# ProPrj_PGEKI_MAIN_2025-10-30.net
KiCad netlist of a schematic drawn in EasyEDA Pro
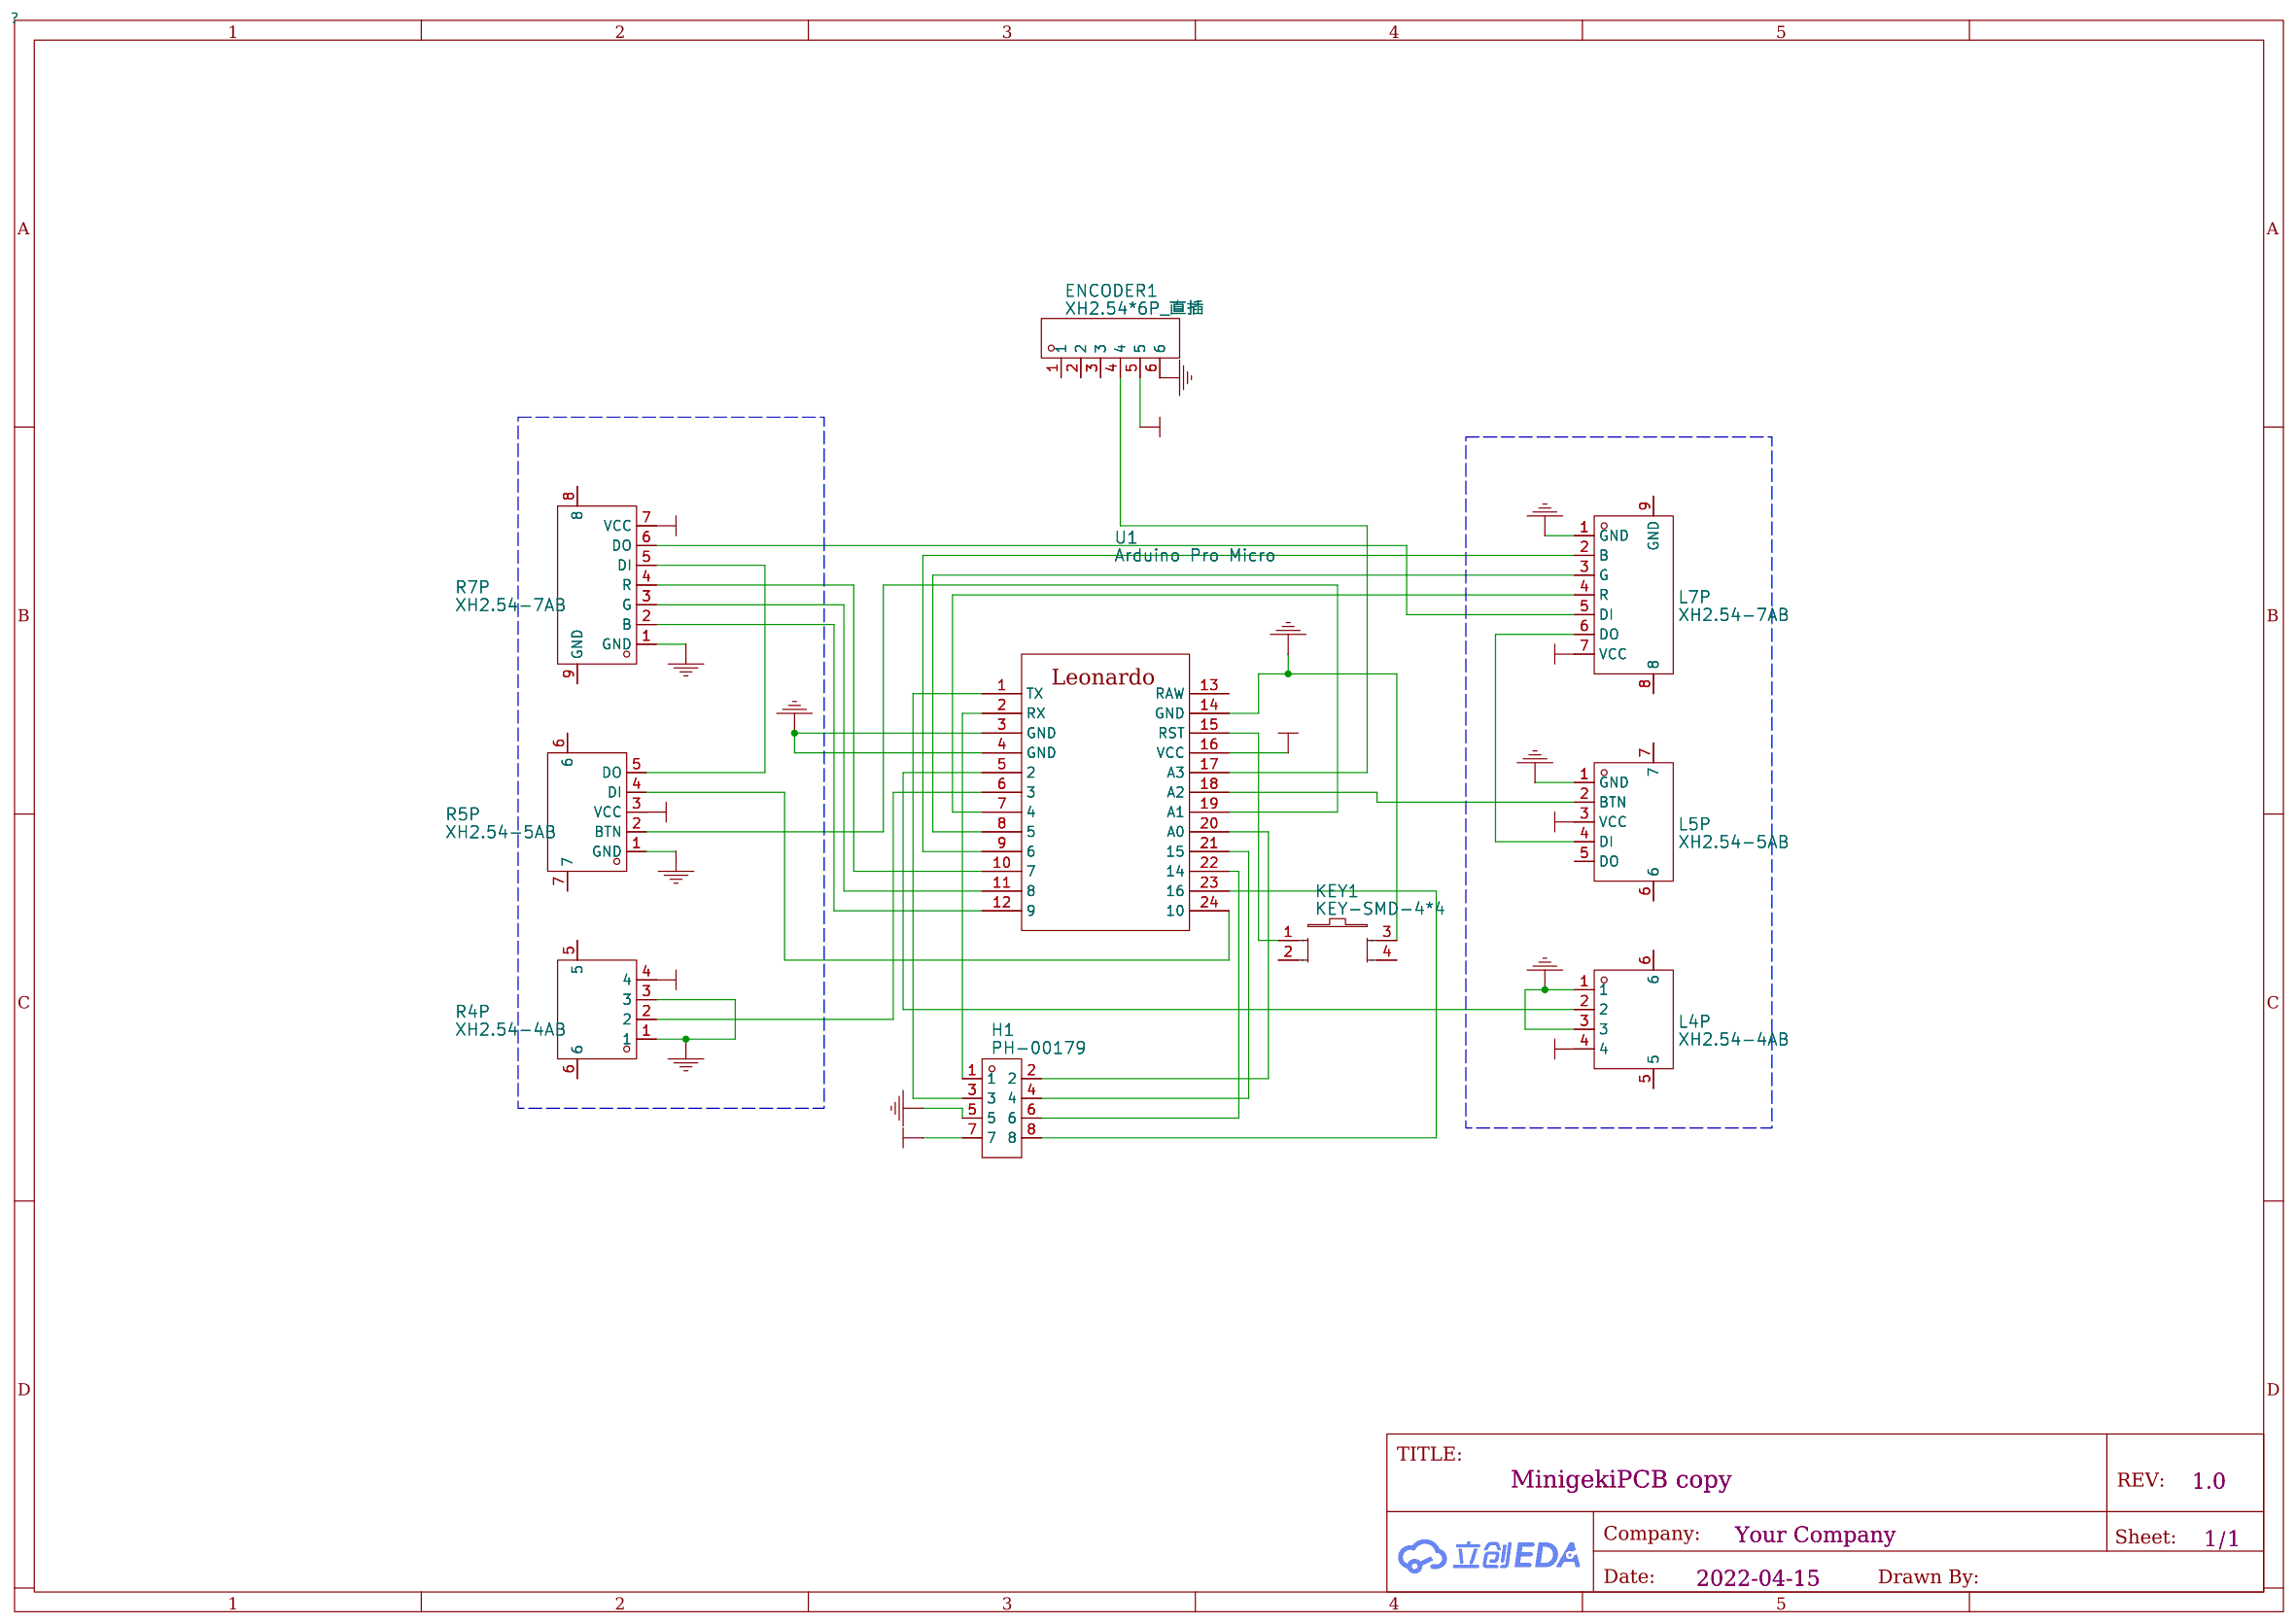
[diagram p0: main]
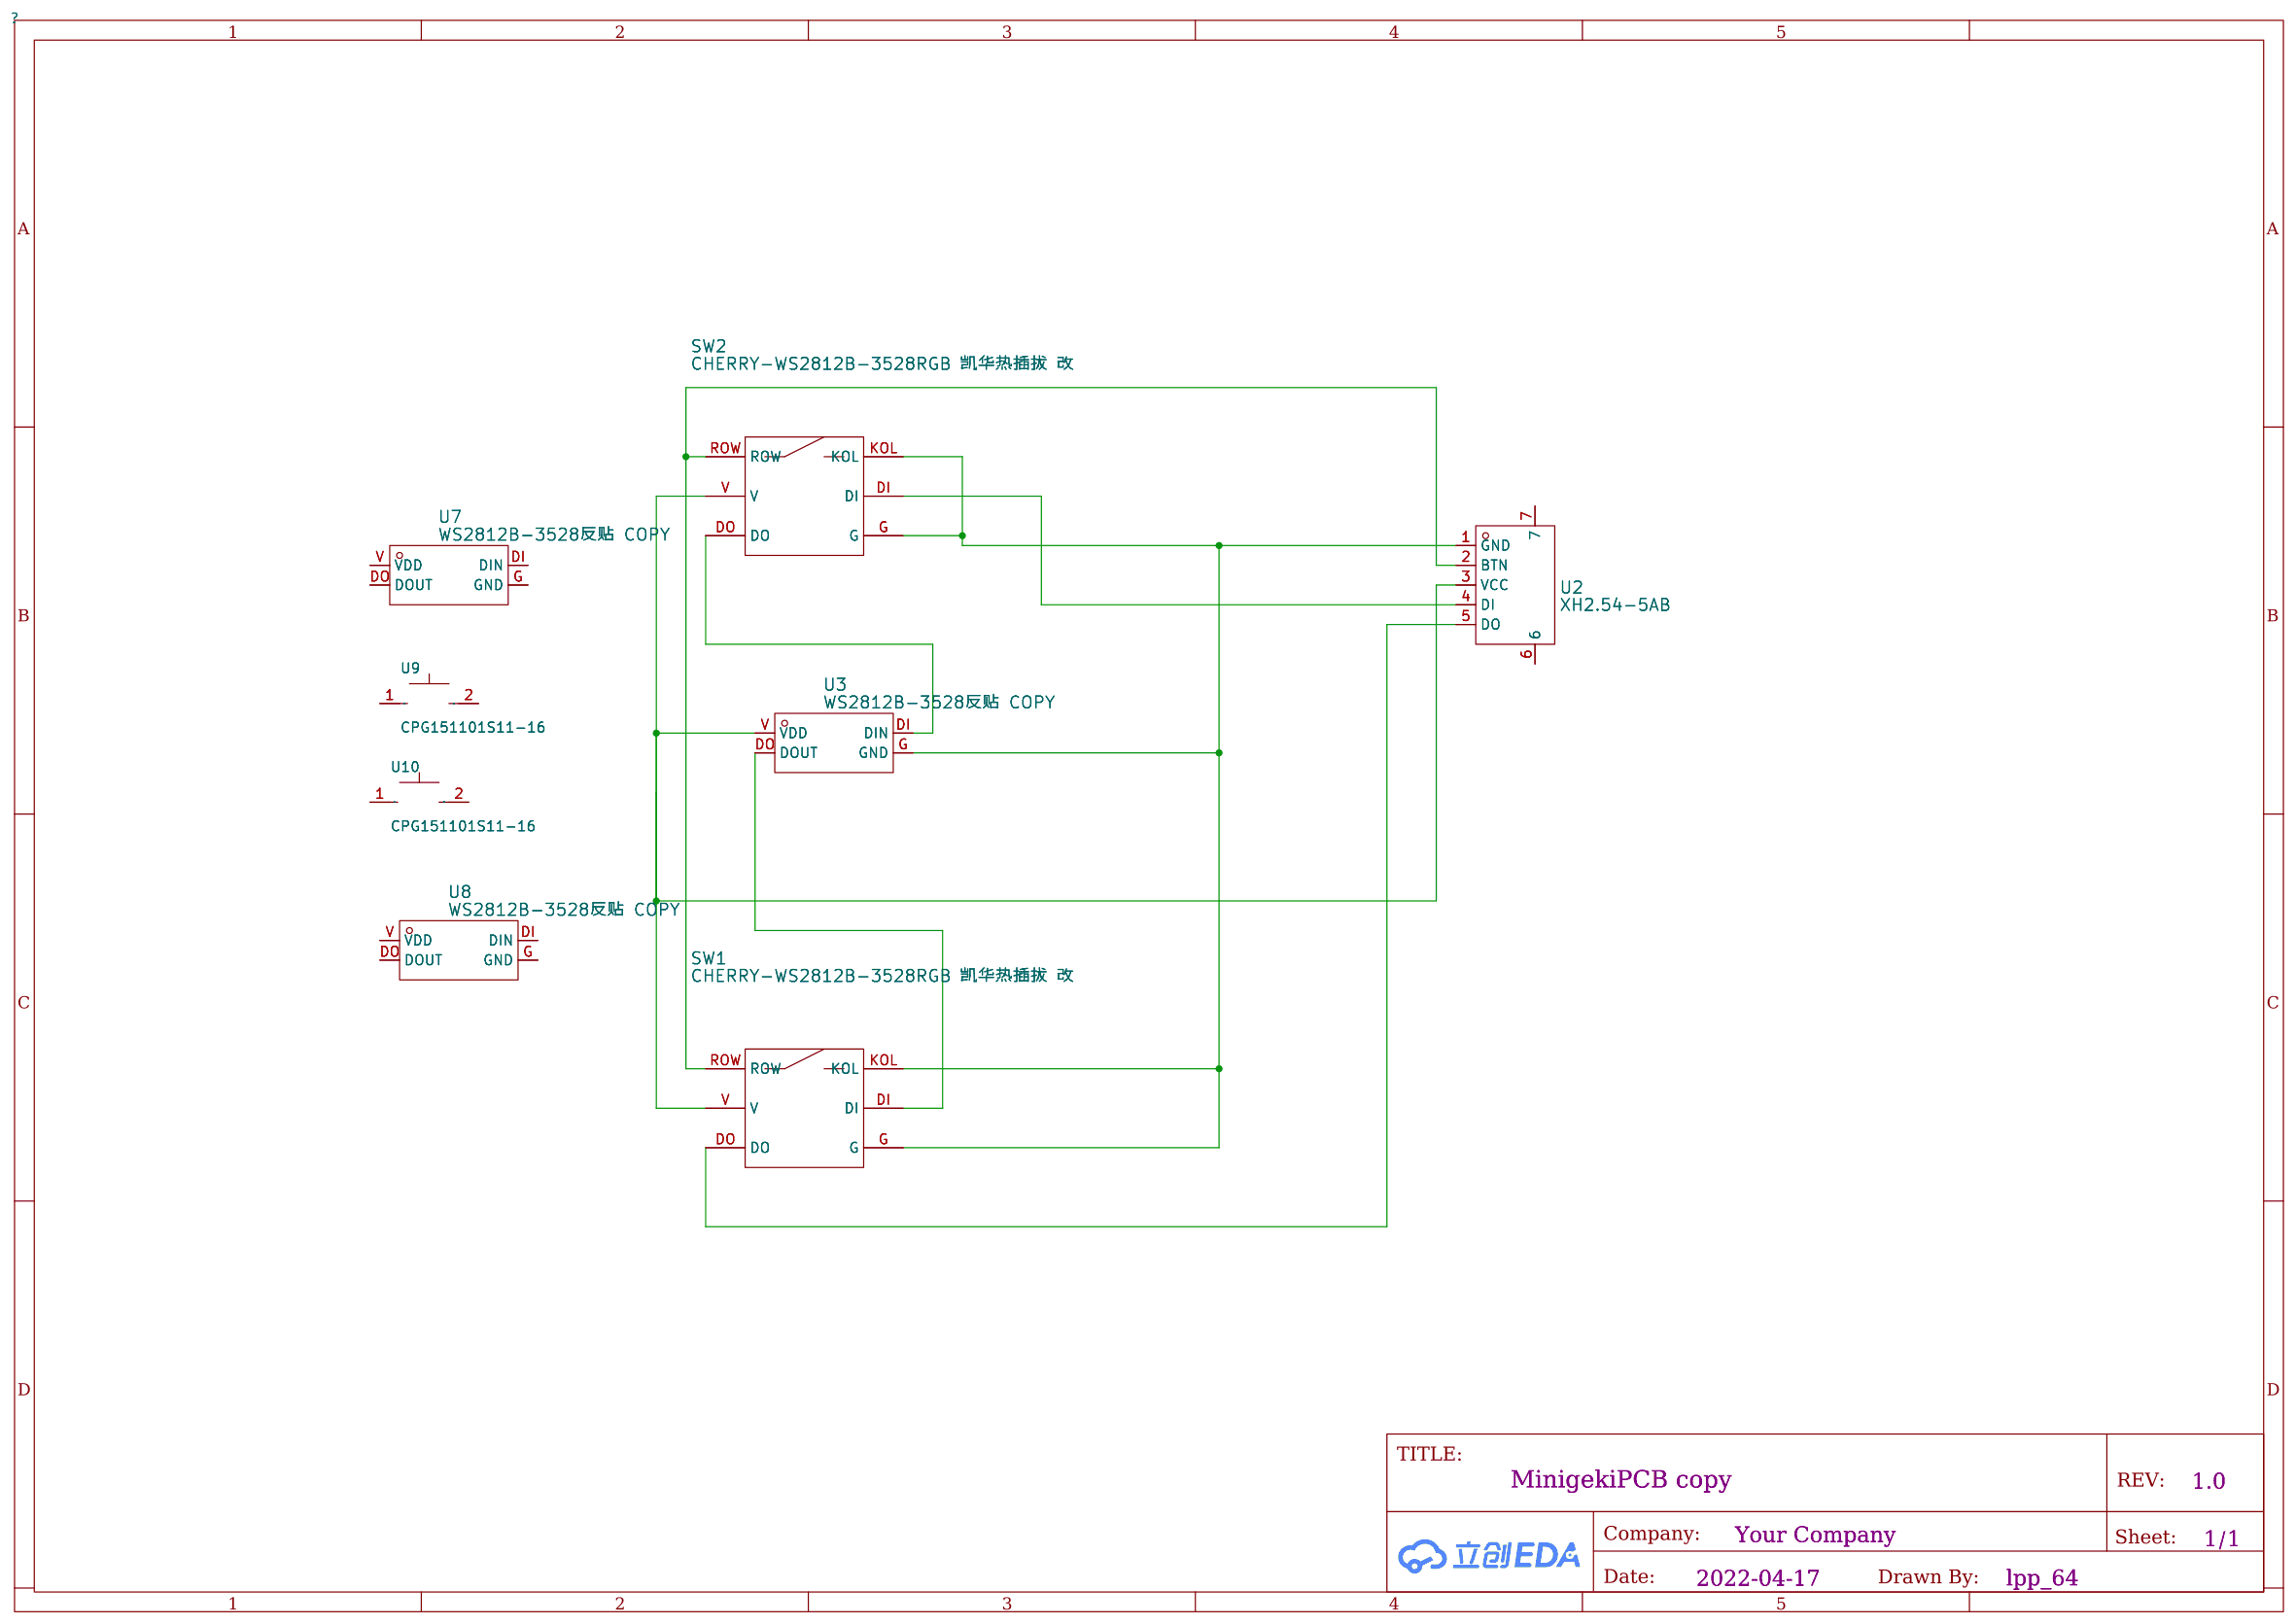
[diagram p1: Sheet_2]
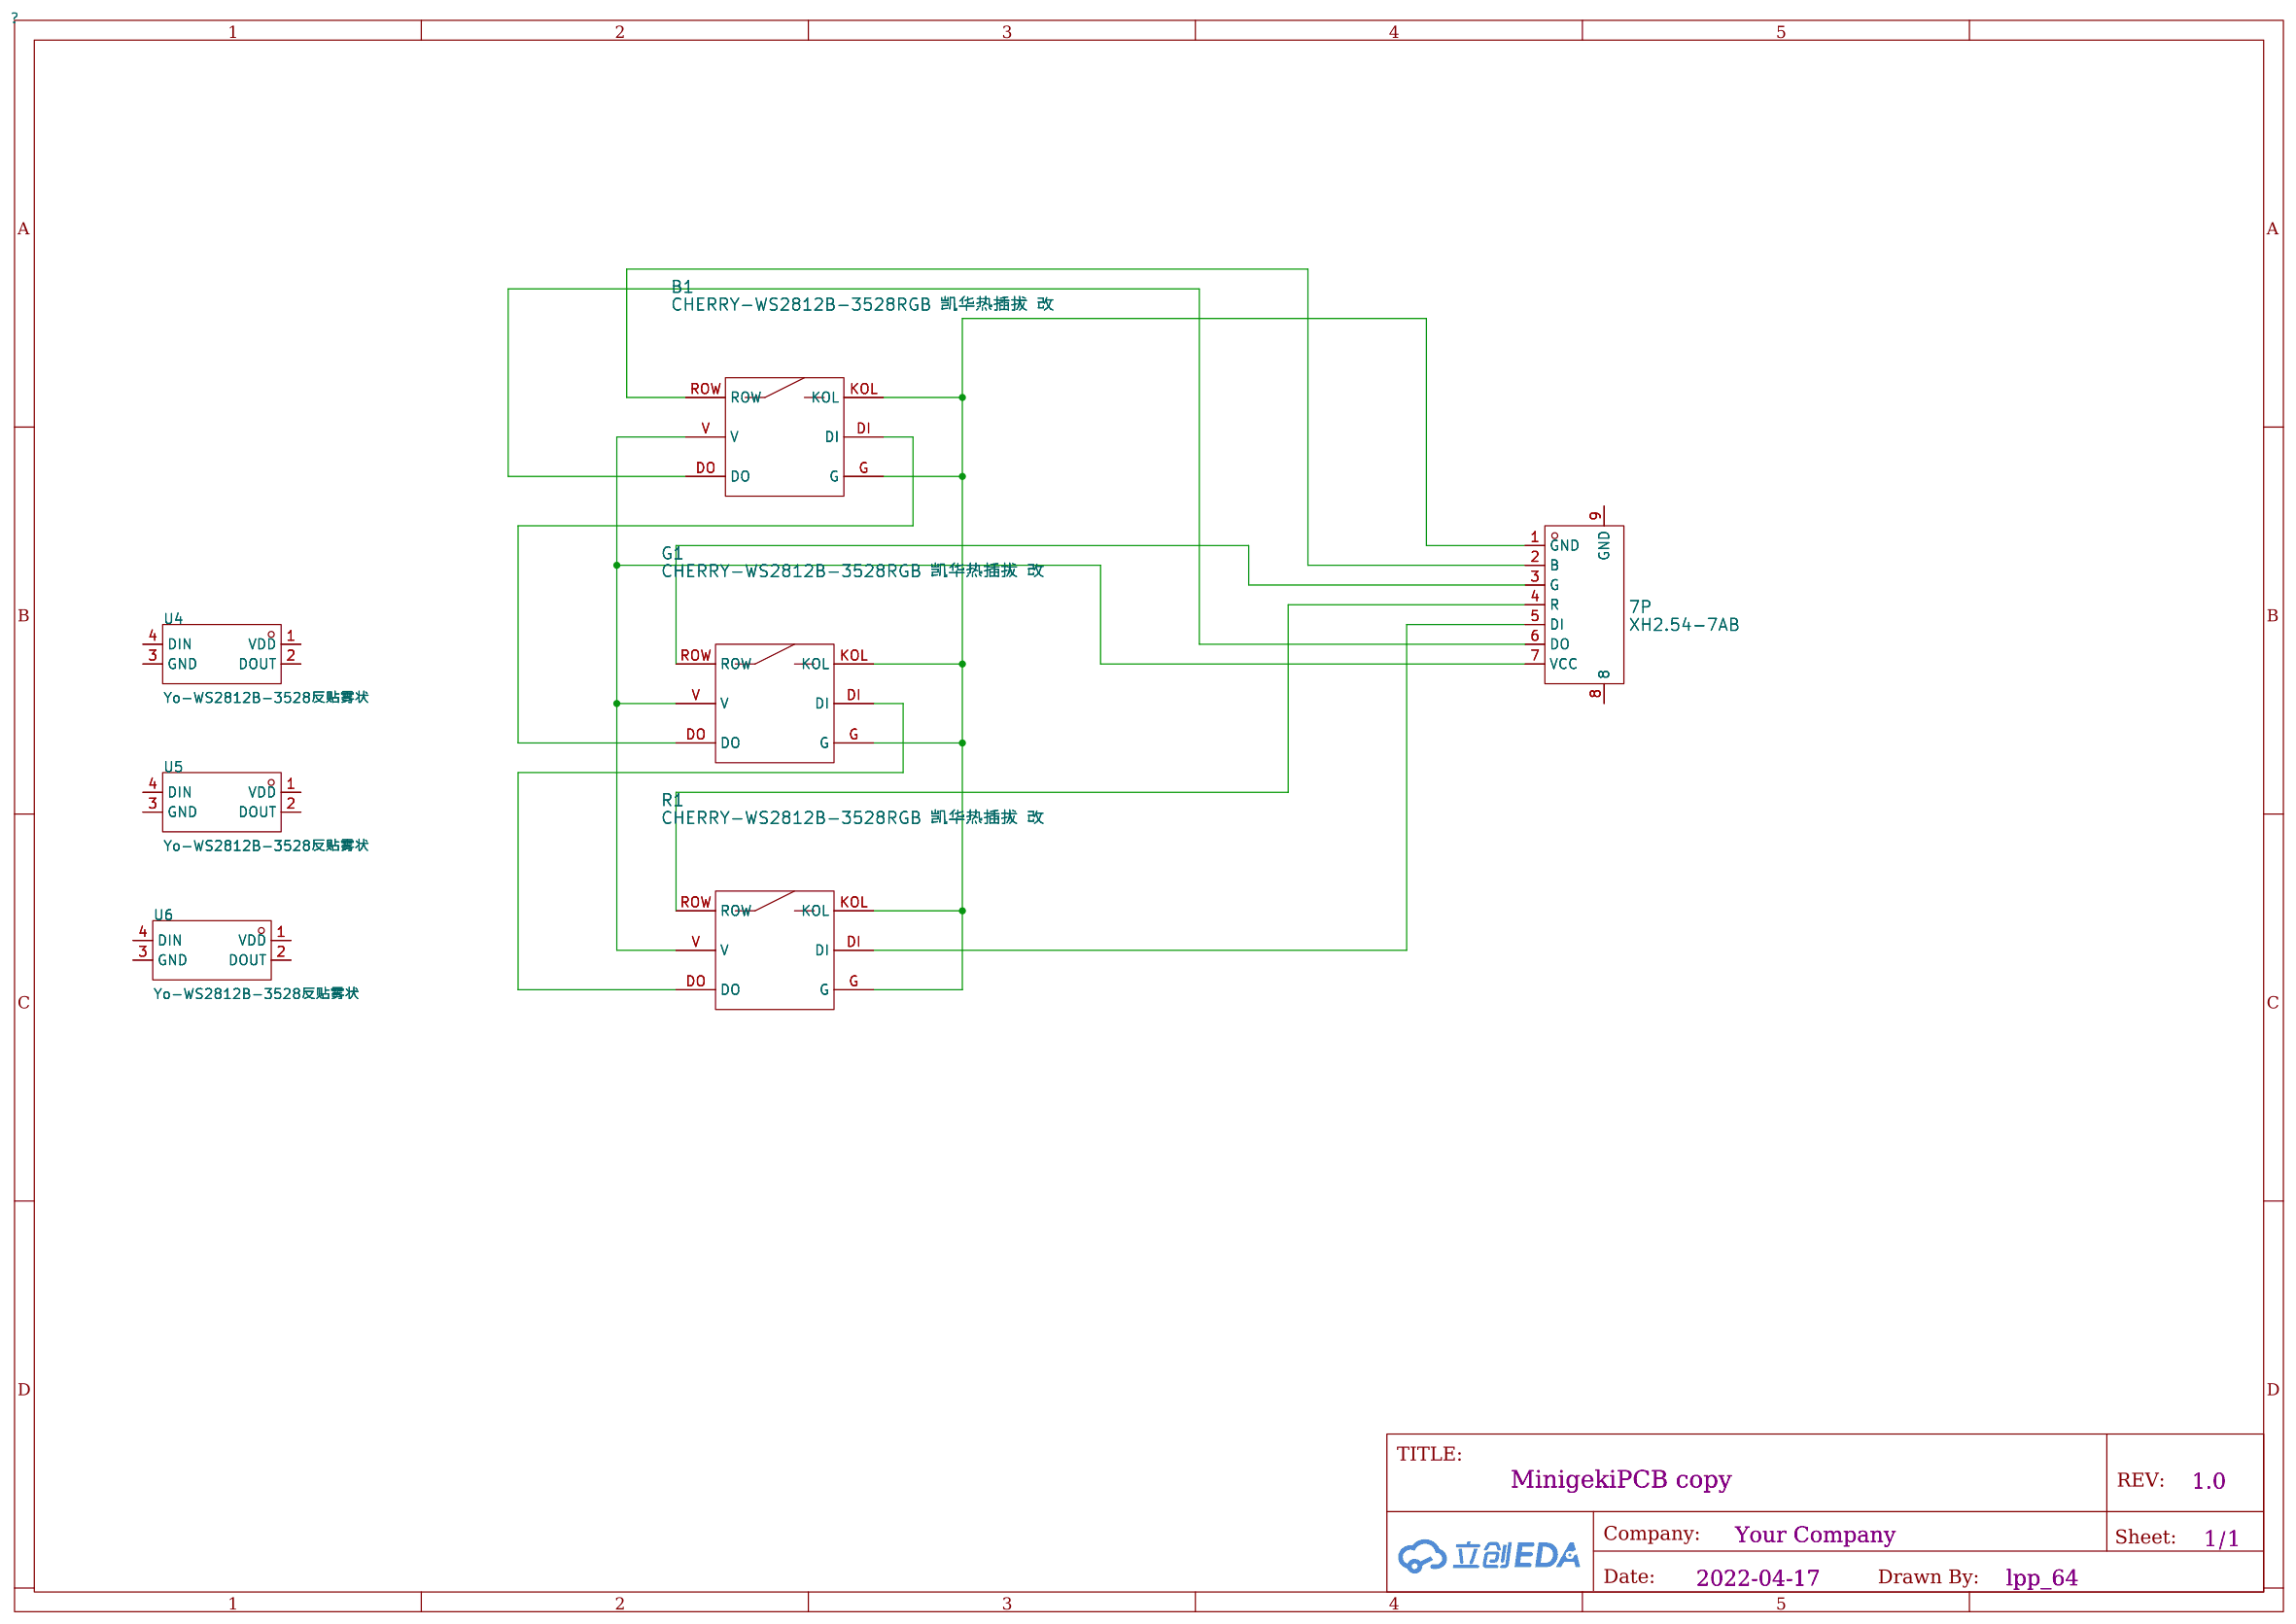
[diagram p2: Sheet_3]

(export (version "E")
  (design (tool "Eeschema 10.0.6"))
  (components
    (comp (ref "ENCODER1")
      (value "XH2.54*6P_直插")
      (footprint "easyedapro:CONN-TH_XH2.54-6P")
      (libsource (lib "easyedapro") (part "XH2.54*6P_直插"))
    )
    (comp (ref "H1")
      (value "PH-00179")
      (footprint "easyedapro:HDR-TH_8P-P2.54-V-M-R2-C4-S2.54")
      (fields (field (name "Manufacturer") "Liansheng(连盛)"))
      (libsource (lib "easyedapro") (part "PH-00179"))
    )
    (comp (ref "KEY1")
      (value "KEY-SMD-4*4")
      (footprint "easyedapro:SW-SMD_4P-L5.2-W5.2-P3.70-LS6.5")
      (libsource (lib "easyedapro") (part "KEY-SMD-4*4"))
    )
    (comp (ref "L4P")
      (value "XH2.54-4AB")
      (footprint "easyedapro:CONN-SMD_4P-P2.54_XH2.54-4AB")
      (fields (field (name "Manufacturer") "Boom Precision Elec"))
      (libsource (lib "easyedapro") (part "XH2.54-4AB"))
    )
    (comp (ref "L5P")
      (value "XH2.54-5AB")
      (footprint "easyedapro:CONN-SMD_5P-P2.54_XH2.54-5AB")
      (fields (field (name "Manufacturer") "Boom Precision Elec"))
      (libsource (lib "easyedapro") (part "XH2.54-5AB"))
    )
    (comp (ref "L7P")
      (value "XH2.54-7AB")
      (footprint "easyedapro:CONN-SMD_7P-P2.54_XH2.54-7AB")
      (fields (field (name "Manufacturer") "Boom Precision Elec"))
      (libsource (lib "easyedapro") (part "XH2.54-7AB"))
    )
    (comp (ref "R4P")
      (value "XH2.54-4AB")
      (footprint "easyedapro:CONN-SMD_4P-P2.54_XH2.54-4AB")
      (fields (field (name "Manufacturer") "Boom Precision Elec"))
      (libsource (lib "easyedapro") (part "XH2.54-4AB"))
    )
    (comp (ref "R5P")
      (value "XH2.54-5AB")
      (footprint "easyedapro:CONN-SMD_5P-P2.54_XH2.54-5AB")
      (fields (field (name "Manufacturer") "Boom Precision Elec"))
      (libsource (lib "easyedapro") (part "XH2.54-5AB"))
    )
    (comp (ref "R7P")
      (value "XH2.54-7AB")
      (footprint "easyedapro:CONN-SMD_7P-P2.54_XH2.54-7AB")
      (fields (field (name "Manufacturer") "Boom Precision Elec"))
      (libsource (lib "easyedapro") (part "XH2.54-7AB"))
    )
    (comp (ref "U1")
      (value "Arduino Pro Micro")
      (footprint "easyedapro:PROMICRO")
      (libsource (lib "easyedapro") (part "Arduino Pro Micro"))
    )
    (comp (ref "SW1")
      (value "CHERRY-WS2812B-3528RGB 凯华热插拔 改")
      (footprint "easyedapro:凯华热插拔-WS2812-3528灯反贴-带二极管-KAILH-IN4148-3528")
      (fields (field (name "Manufacturer Part") "CherryMX"))
      (libsource (lib "easyedapro") (part "CHERRY-WS2812B-3528RGB 凯华热插拔 改 无二极管"))
    )
    (comp (ref "SW2")
      (value "CHERRY-WS2812B-3528RGB 凯华热插拔 改")
      (footprint "easyedapro:凯华热插拔-WS2812-3528灯反贴-带二极管-KAILH-IN4148-3528")
      (fields (field (name "Manufacturer Part") "CherryMX"))
      (libsource (lib "easyedapro") (part "CHERRY-WS2812B-3528RGB 凯华热插拔 改 无二极管"))
    )
    (comp (ref "U2")
      (value "XH2.54-5AB")
      (footprint "easyedapro:CONN-SMD_5P-P2.54_XH2.54-5AB")
      (fields (field (name "Manufacturer") "Boom Precision Elec"))
      (libsource (lib "easyedapro") (part "XH2.54-5AB"))
    )
    (comp (ref "U3")
      (value "WS2812B-3528反贴 COPY")
      (footprint "easyedapro:WS2812-3528-反贴")
      (fields (field (name "Manufacturer Part") "Yo-WS2812B-3528反贴雾状"))
      (libsource (lib "easyedapro") (part "WS2812B-3528反贴 COPY"))
    )
    (comp (ref "U7")
      (value "WS2812B-3528反贴 COPY")
      (footprint "easyedapro:WS2812-3528-反贴")
      (fields (field (name "Manufacturer Part") "Yo-WS2812B-3528反贴雾状"))
      (libsource (lib "easyedapro") (part "WS2812B-3528反贴 COPY"))
    )
    (comp (ref "U8")
      (value "WS2812B-3528反贴 COPY")
      (footprint "easyedapro:WS2812-3528-反贴")
      (fields (field (name "Manufacturer Part") "Yo-WS2812B-3528反贴雾状"))
      (libsource (lib "easyedapro") (part "WS2812B-3528反贴 COPY"))
    )
    (comp (ref "U9")
      (value "CPG151101S11-16")
      (footprint "easyedapro:SMD_KEYBOARD-SW")
      (description "轴类型:-;工作电压:2V~12V;操作力:-;触底力:-;触发行程:-;总行程:-;针脚数:-;机械寿命:-;工作温度:-;")
      (fields (field (name "Manufacturer") "Kailh(凯华)"))
      (libsource (lib "easyedapro") (part "CPG151101S11-16"))
    )
    (comp (ref "U10")
      (value "CPG151101S11-16")
      (footprint "easyedapro:SMD_KEYBOARD-SW")
      (description "轴类型:-;工作电压:2V~12V;操作力:-;触底力:-;触发行程:-;总行程:-;针脚数:-;机械寿命:-;工作温度:-;")
      (fields (field (name "Manufacturer") "Kailh(凯华)"))
      (libsource (lib "easyedapro") (part "CPG151101S11-16"))
    )
    (comp (ref "7P")
      (value "XH2.54-7AB")
      (footprint "easyedapro:CONN-SMD_7P-P2.54_XH2.54-7AB")
      (fields (field (name "Manufacturer") "Boom Precision Elec"))
      (libsource (lib "easyedapro") (part "XH2.54-7AB"))
    )
    (comp (ref "B1")
      (value "CHERRY-WS2812B-3528RGB 凯华热插拔 改")
      (footprint "easyedapro:凯华热插拔-WS2812-3528灯反贴-带二极管-KAILH-IN4148-3528")
      (fields (field (name "Manufacturer Part") "CherryMX"))
      (libsource (lib "easyedapro") (part "CHERRY-WS2812B-3528RGB 凯华热插拔 改 无二极管"))
    )
    (comp (ref "G1")
      (value "CHERRY-WS2812B-3528RGB 凯华热插拔 改")
      (footprint "easyedapro:凯华热插拔-WS2812-3528灯反贴-带二极管-KAILH-IN4148-3528")
      (fields (field (name "Manufacturer Part") "CherryMX"))
      (libsource (lib "easyedapro") (part "CHERRY-WS2812B-3528RGB 凯华热插拔 改 无二极管"))
    )
    (comp (ref "R1")
      (value "CHERRY-WS2812B-3528RGB 凯华热插拔 改")
      (footprint "easyedapro:凯华热插拔-WS2812-3528灯反贴-带二极管-KAILH-IN4148-3528")
      (fields (field (name "Manufacturer Part") "CherryMX"))
      (libsource (lib "easyedapro") (part "CHERRY-WS2812B-3528RGB 凯华热插拔 改 无二极管"))
    )
    (comp (ref "U4")
      (value "Yo-WS2812B-3528反贴雾状")
      (footprint "easyedapro:LED-SMD_L3.2-W2.8-BR_DY-S352818")
      (libsource (lib "easyedapro") (part "YO-WS2812B-3528_C9900003682"))
    )
    (comp (ref "U5")
      (value "Yo-WS2812B-3528反贴雾状")
      (footprint "easyedapro:LED-SMD_L3.2-W2.8-BR_DY-S352818")
      (libsource (lib "easyedapro") (part "YO-WS2812B-3528_C9900003682"))
    )
    (comp (ref "U6")
      (value "Yo-WS2812B-3528反贴雾状")
      (footprint "easyedapro:LED-SMD_L3.2-W2.8-BR_DY-S352818")
      (libsource (lib "easyedapro") (part "YO-WS2812B-3528_C9900003682"))
    )
  )
  (nets
    (net (code "1") (name "GND") (class "Default")
      (node (ref "ENCODER1") (pin "6") (pinfunction "6_6") (pintype "input"))
      (node (ref "H1") (pin "5") (pinfunction "5_5") (pintype "input"))
      (node (ref "KEY1") (pin "3") (pinfunction "3_3") (pintype "input"))
      (node (ref "L4P") (pin "1") (pinfunction "1_1") (pintype "input"))
      (node (ref "L4P") (pin "3") (pinfunction "3_3") (pintype "input"))
      (node (ref "L5P") (pin "1") (pinfunction "GND_1") (pintype "input"))
      (node (ref "L7P") (pin "1") (pinfunction "GND_1") (pintype "input"))
      (node (ref "R4P") (pin "1") (pinfunction "1_1") (pintype "input"))
      (node (ref "R4P") (pin "3") (pinfunction "3_3") (pintype "input"))
      (node (ref "R5P") (pin "1") (pinfunction "GND_1") (pintype "input"))
      (node (ref "R7P") (pin "1") (pinfunction "GND_1") (pintype "input"))
      (node (ref "U1") (pin "14") (pinfunction "GND_14") (pintype "input"))
      (node (ref "U1") (pin "3") (pinfunction "GND_3") (pintype "input"))
      (node (ref "U1") (pin "4") (pinfunction "GND_4") (pintype "input"))
    )
    (net (code "2") (name "Net-(7P-B)") (class "Default")
      (node (ref "7P") (pin "2") (pinfunction "B_2") (pintype "input"))
      (node (ref "B1") (pin "ROW") (pinfunction "ROW_ROW") (pintype "input"))
    )
    (net (code "3") (name "Net-(7P-DI)") (class "Default")
      (node (ref "7P") (pin "5") (pinfunction "DI_5") (pintype "input"))
      (node (ref "R1") (pin "DI") (pinfunction "DI_DI") (pintype "input"))
    )
    (net (code "4") (name "Net-(7P-DO)") (class "Default")
      (node (ref "7P") (pin "6") (pinfunction "DO_6") (pintype "input"))
      (node (ref "B1") (pin "DO") (pinfunction "DO_DO") (pintype "input"))
    )
    (net (code "5") (name "Net-(7P-G)") (class "Default")
      (node (ref "7P") (pin "3") (pinfunction "G_3") (pintype "input"))
      (node (ref "G1") (pin "ROW") (pinfunction "ROW_ROW") (pintype "input"))
    )
    (net (code "6") (name "Net-(7P-GND-Pad1)") (class "Default")
      (node (ref "7P") (pin "1") (pinfunction "GND_1") (pintype "input"))
      (node (ref "B1") (pin "G") (pinfunction "G_G") (pintype "input"))
      (node (ref "B1") (pin "KOL") (pinfunction "KOL_KOL") (pintype "input"))
      (node (ref "G1") (pin "G") (pinfunction "G_G") (pintype "input"))
      (node (ref "G1") (pin "KOL") (pinfunction "KOL_KOL") (pintype "input"))
      (node (ref "R1") (pin "G") (pinfunction "G_G") (pintype "input"))
      (node (ref "R1") (pin "KOL") (pinfunction "KOL_KOL") (pintype "input"))
    )
    (net (code "7") (name "Net-(7P-R)") (class "Default")
      (node (ref "7P") (pin "4") (pinfunction "R_4") (pintype "input"))
      (node (ref "R1") (pin "ROW") (pinfunction "ROW_ROW") (pintype "input"))
    )
    (net (code "8") (name "Net-(7P-VCC)") (class "Default")
      (node (ref "7P") (pin "7") (pinfunction "VCC_7") (pintype "input"))
      (node (ref "B1") (pin "V") (pinfunction "V_V") (pintype "input"))
      (node (ref "G1") (pin "V") (pinfunction "V_V") (pintype "input"))
      (node (ref "R1") (pin "V") (pinfunction "V_V") (pintype "input"))
    )
    (net (code "9") (name "Net-(B1-PadDI)") (class "Default")
      (node (ref "B1") (pin "DI") (pinfunction "DI_DI") (pintype "input"))
      (node (ref "G1") (pin "DO") (pinfunction "DO_DO") (pintype "input"))
    )
    (net (code "10") (name "Net-(G1-PadDI)") (class "Default")
      (node (ref "G1") (pin "DI") (pinfunction "DI_DI") (pintype "input"))
      (node (ref "R1") (pin "DO") (pinfunction "DO_DO") (pintype "input"))
    )
    (net (code "11") (name "Net-(L5P-BTN)") (class "Default")
      (node (ref "L5P") (pin "2") (pinfunction "BTN_2") (pintype "input"))
      (node (ref "U1") (pin "18") (pinfunction "A2_18") (pintype "input"))
    )
    (net (code "12") (name "Net-(L5P-DI)") (class "Default")
      (node (ref "L5P") (pin "4") (pinfunction "DI_4") (pintype "input"))
      (node (ref "L7P") (pin "6") (pinfunction "DO_6") (pintype "input"))
    )
    (net (code "13") (name "Net-(L7P-B)") (class "Default")
      (node (ref "L7P") (pin "2") (pinfunction "B_2") (pintype "input"))
      (node (ref "U1") (pin "9") (pinfunction "6_9") (pintype "input"))
    )
    (net (code "14") (name "Net-(L7P-DI)") (class "Default")
      (node (ref "L7P") (pin "5") (pinfunction "DI_5") (pintype "input"))
      (node (ref "R7P") (pin "6") (pinfunction "DO_6") (pintype "input"))
    )
    (net (code "15") (name "Net-(L7P-G)") (class "Default")
      (node (ref "L7P") (pin "3") (pinfunction "G_3") (pintype "input"))
      (node (ref "U1") (pin "8") (pinfunction "5_8") (pintype "input"))
    )
    (net (code "16") (name "Net-(L7P-R)") (class "Default")
      (node (ref "L7P") (pin "4") (pinfunction "R_4") (pintype "input"))
      (node (ref "U1") (pin "7") (pinfunction "4_7") (pintype "input"))
    )
    (net (code "17") (name "Net-(R5P-BTN)") (class "Default")
      (node (ref "R5P") (pin "2") (pinfunction "BTN_2") (pintype "input"))
      (node (ref "U1") (pin "19") (pinfunction "A1_19") (pintype "input"))
    )
    (net (code "18") (name "Net-(R5P-DI)") (class "Default")
      (node (ref "R5P") (pin "4") (pinfunction "DI_4") (pintype "input"))
      (node (ref "U1") (pin "24") (pinfunction "10_24") (pintype "input"))
    )
    (net (code "19") (name "Net-(R5P-DO)") (class "Default")
      (node (ref "R5P") (pin "5") (pinfunction "DO_5") (pintype "input"))
      (node (ref "R7P") (pin "5") (pinfunction "DI_5") (pintype "input"))
    )
    (net (code "20") (name "Net-(R7P-B)") (class "Default")
      (node (ref "R7P") (pin "2") (pinfunction "B_2") (pintype "input"))
      (node (ref "U1") (pin "12") (pinfunction "9_12") (pintype "input"))
    )
    (net (code "21") (name "Net-(R7P-G)") (class "Default")
      (node (ref "R7P") (pin "3") (pinfunction "G_3") (pintype "input"))
      (node (ref "U1") (pin "11") (pinfunction "8_11") (pintype "input"))
    )
    (net (code "22") (name "Net-(R7P-R)") (class "Default")
      (node (ref "R7P") (pin "4") (pinfunction "R_4") (pintype "input"))
      (node (ref "U1") (pin "10") (pinfunction "7_10") (pintype "input"))
    )
    (net (code "23") (name "Net-(U1-2)") (class "Default")
      (node (ref "L4P") (pin "2") (pinfunction "2_2") (pintype "input"))
      (node (ref "U1") (pin "5") (pinfunction "2_5") (pintype "input"))
    )
    (net (code "24") (name "Net-(U1-3)") (class "Default")
      (node (ref "R4P") (pin "2") (pinfunction "2_2") (pintype "input"))
      (node (ref "U1") (pin "6") (pinfunction "3_6") (pintype "input"))
    )
    (net (code "25") (name "Net-(U1-14)") (class "Default")
      (node (ref "H1") (pin "6") (pinfunction "6_6") (pintype "input"))
      (node (ref "U1") (pin "22") (pinfunction "14_22") (pintype "input"))
    )
    (net (code "26") (name "Net-(U1-15)") (class "Default")
      (node (ref "H1") (pin "4") (pinfunction "4_4") (pintype "input"))
      (node (ref "U1") (pin "21") (pinfunction "15_21") (pintype "input"))
    )
    (net (code "27") (name "Net-(U1-16)") (class "Default")
      (node (ref "H1") (pin "8") (pinfunction "8_8") (pintype "input"))
      (node (ref "U1") (pin "23") (pinfunction "16_23") (pintype "input"))
    )
    (net (code "28") (name "Net-(U1-A0)") (class "Default")
      (node (ref "H1") (pin "2") (pinfunction "2_2") (pintype "input"))
      (node (ref "U1") (pin "20") (pinfunction "A0_20") (pintype "input"))
    )
    (net (code "29") (name "Net-(U1-A3)") (class "Default")
      (node (ref "ENCODER1") (pin "4") (pinfunction "4_4") (pintype "input"))
      (node (ref "U1") (pin "17") (pinfunction "A3_17") (pintype "input"))
    )
    (net (code "30") (name "Net-(U1-RST)") (class "Default")
      (node (ref "KEY1") (pin "1") (pinfunction "1_1") (pintype "input"))
      (node (ref "U1") (pin "15") (pinfunction "RST_15") (pintype "input"))
    )
    (net (code "31") (name "Net-(U1-RX)") (class "Default")
      (node (ref "H1") (pin "1") (pinfunction "1_1") (pintype "input"))
      (node (ref "U1") (pin "2") (pinfunction "RX_2") (pintype "input"))
    )
    (net (code "32") (name "Net-(U1-TX)") (class "Default")
      (node (ref "H1") (pin "3") (pinfunction "3_3") (pintype "input"))
      (node (ref "U1") (pin "1") (pinfunction "TX_1") (pintype "input"))
    )
    (net (code "33") (name "Net-(U2-BTN)") (class "Default")
      (node (ref "SW1") (pin "ROW") (pinfunction "ROW_ROW") (pintype "input"))
      (node (ref "SW2") (pin "ROW") (pinfunction "ROW_ROW") (pintype "input"))
      (node (ref "U2") (pin "2") (pinfunction "BTN_2") (pintype "input"))
    )
    (net (code "34") (name "Net-(U2-DI)") (class "Default")
      (node (ref "SW2") (pin "DI") (pinfunction "DI_DI") (pintype "input"))
      (node (ref "U2") (pin "4") (pinfunction "DI_4") (pintype "input"))
    )
    (net (code "35") (name "Net-(U2-DO)") (class "Default")
      (node (ref "SW1") (pin "DO") (pinfunction "DO_DO") (pintype "input"))
      (node (ref "U2") (pin "5") (pinfunction "DO_5") (pintype "input"))
    )
    (net (code "36") (name "Net-(U2-GND)") (class "Default")
      (node (ref "SW1") (pin "G") (pinfunction "G_G") (pintype "input"))
      (node (ref "SW1") (pin "KOL") (pinfunction "KOL_KOL") (pintype "input"))
      (node (ref "SW2") (pin "G") (pinfunction "G_G") (pintype "input"))
      (node (ref "SW2") (pin "KOL") (pinfunction "KOL_KOL") (pintype "input"))
      (node (ref "U2") (pin "1") (pinfunction "GND_1") (pintype "input"))
      (node (ref "U3") (pin "G") (pinfunction "GND_G") (pintype "input"))
    )
    (net (code "37") (name "Net-(U2-VCC)") (class "Default")
      (node (ref "SW1") (pin "V") (pinfunction "V_V") (pintype "input"))
      (node (ref "SW2") (pin "V") (pinfunction "V_V") (pintype "input"))
      (node (ref "U2") (pin "3") (pinfunction "VCC_3") (pintype "input"))
      (node (ref "U3") (pin "V") (pinfunction "VDD_V") (pintype "input"))
    )
    (net (code "38") (name "Net-(U3-DIN)") (class "Default")
      (node (ref "SW2") (pin "DO") (pinfunction "DO_DO") (pintype "input"))
      (node (ref "U3") (pin "DI") (pinfunction "DIN_DI") (pintype "input"))
    )
    (net (code "39") (name "Net-(U3-DOUT)") (class "Default")
      (node (ref "SW1") (pin "DI") (pinfunction "DI_DI") (pintype "input"))
      (node (ref "U3") (pin "DO") (pinfunction "DOUT_DO") (pintype "input"))
    )
    (net (code "40") (name "VCC") (class "Default")
      (node (ref "ENCODER1") (pin "5") (pinfunction "5_5") (pintype "input"))
      (node (ref "H1") (pin "7") (pinfunction "7_7") (pintype "input"))
      (node (ref "L4P") (pin "4") (pinfunction "4_4") (pintype "input"))
      (node (ref "L5P") (pin "3") (pinfunction "VCC_3") (pintype "input"))
      (node (ref "L7P") (pin "7") (pinfunction "VCC_7") (pintype "input"))
      (node (ref "R4P") (pin "4") (pinfunction "4_4") (pintype "input"))
      (node (ref "R5P") (pin "3") (pinfunction "VCC_3") (pintype "input"))
      (node (ref "R7P") (pin "7") (pinfunction "VCC_7") (pintype "input"))
      (node (ref "U1") (pin "16") (pinfunction "VCC_16") (pintype "input"))
    )
    (net (code "41") (name "unconnected-(7P-GND-Pad9)") (class "Default")
      (node (ref "7P") (pin "9") (pinfunction "GND_9") (pintype "input"))
    )
    (net (code "42") (name "unconnected-(7P-Pad8)") (class "Default")
      (node (ref "7P") (pin "8") (pinfunction "8_8") (pintype "input"))
    )
    (net (code "43") (name "unconnected-(ENCODER1-Pad1)") (class "Default")
      (node (ref "ENCODER1") (pin "1") (pinfunction "1_1") (pintype "input"))
    )
    (net (code "44") (name "unconnected-(ENCODER1-Pad2)") (class "Default")
      (node (ref "ENCODER1") (pin "2") (pinfunction "2_2") (pintype "input"))
    )
    (net (code "45") (name "unconnected-(ENCODER1-Pad3)") (class "Default")
      (node (ref "ENCODER1") (pin "3") (pinfunction "3_3") (pintype "input"))
    )
    (net (code "46") (name "unconnected-(KEY1-Pad2)") (class "Default")
      (node (ref "KEY1") (pin "2") (pinfunction "2_2") (pintype "input"))
    )
    (net (code "47") (name "unconnected-(KEY1-Pad4)") (class "Default")
      (node (ref "KEY1") (pin "4") (pinfunction "4_4") (pintype "input"))
    )
    (net (code "48") (name "unconnected-(L4P-Pad5)") (class "Default")
      (node (ref "L4P") (pin "5") (pinfunction "5_5") (pintype "input"))
    )
    (net (code "49") (name "unconnected-(L4P-Pad6)") (class "Default")
      (node (ref "L4P") (pin "6") (pinfunction "6_6") (pintype "input"))
    )
    (net (code "50") (name "unconnected-(L5P-DO-Pad5)") (class "Default")
      (node (ref "L5P") (pin "5") (pinfunction "DO_5") (pintype "input"))
    )
    (net (code "51") (name "unconnected-(L5P-Pad6)") (class "Default")
      (node (ref "L5P") (pin "6") (pinfunction "6_6") (pintype "input"))
    )
    (net (code "52") (name "unconnected-(L5P-Pad7)") (class "Default")
      (node (ref "L5P") (pin "7") (pinfunction "7_7") (pintype "input"))
    )
    (net (code "53") (name "unconnected-(L7P-GND-Pad9)") (class "Default")
      (node (ref "L7P") (pin "9") (pinfunction "GND_9") (pintype "input"))
    )
    (net (code "54") (name "unconnected-(L7P-Pad8)") (class "Default")
      (node (ref "L7P") (pin "8") (pinfunction "8_8") (pintype "input"))
    )
    (net (code "55") (name "unconnected-(R4P-Pad5)") (class "Default")
      (node (ref "R4P") (pin "5") (pinfunction "5_5") (pintype "input"))
    )
    (net (code "56") (name "unconnected-(R4P-Pad6)") (class "Default")
      (node (ref "R4P") (pin "6") (pinfunction "6_6") (pintype "input"))
    )
    (net (code "57") (name "unconnected-(R5P-Pad6)") (class "Default")
      (node (ref "R5P") (pin "6") (pinfunction "6_6") (pintype "input"))
    )
    (net (code "58") (name "unconnected-(R5P-Pad7)") (class "Default")
      (node (ref "R5P") (pin "7") (pinfunction "7_7") (pintype "input"))
    )
    (net (code "59") (name "unconnected-(R7P-GND-Pad9)") (class "Default")
      (node (ref "R7P") (pin "9") (pinfunction "GND_9") (pintype "input"))
    )
    (net (code "60") (name "unconnected-(R7P-Pad8)") (class "Default")
      (node (ref "R7P") (pin "8") (pinfunction "8_8") (pintype "input"))
    )
    (net (code "61") (name "unconnected-(U1-RAW-Pad13)") (class "Default")
      (node (ref "U1") (pin "13") (pinfunction "RAW_13") (pintype "input"))
    )
    (net (code "62") (name "unconnected-(U2-Pad6)") (class "Default")
      (node (ref "U2") (pin "6") (pinfunction "6_6") (pintype "input"))
    )
    (net (code "63") (name "unconnected-(U2-Pad7)") (class "Default")
      (node (ref "U2") (pin "7") (pinfunction "7_7") (pintype "input"))
    )
    (net (code "64") (name "unconnected-(U4-DIN-Pad4)") (class "Default")
      (node (ref "U4") (pin "4") (pinfunction "DIN_4") (pintype "input"))
    )
    (net (code "65") (name "unconnected-(U4-DOUT-Pad2)") (class "Default")
      (node (ref "U4") (pin "2") (pinfunction "DOUT_2") (pintype "input"))
    )
    (net (code "66") (name "unconnected-(U4-GND-Pad3)") (class "Default")
      (node (ref "U4") (pin "3") (pinfunction "GND_3") (pintype "input"))
    )
    (net (code "67") (name "unconnected-(U4-VDD-Pad1)") (class "Default")
      (node (ref "U4") (pin "1") (pinfunction "VDD_1") (pintype "input"))
    )
    (net (code "68") (name "unconnected-(U5-DIN-Pad4)") (class "Default")
      (node (ref "U5") (pin "4") (pinfunction "DIN_4") (pintype "input"))
    )
    (net (code "69") (name "unconnected-(U5-DOUT-Pad2)") (class "Default")
      (node (ref "U5") (pin "2") (pinfunction "DOUT_2") (pintype "input"))
    )
    (net (code "70") (name "unconnected-(U5-GND-Pad3)") (class "Default")
      (node (ref "U5") (pin "3") (pinfunction "GND_3") (pintype "input"))
    )
    (net (code "71") (name "unconnected-(U5-VDD-Pad1)") (class "Default")
      (node (ref "U5") (pin "1") (pinfunction "VDD_1") (pintype "input"))
    )
    (net (code "72") (name "unconnected-(U6-DIN-Pad4)") (class "Default")
      (node (ref "U6") (pin "4") (pinfunction "DIN_4") (pintype "input"))
    )
    (net (code "73") (name "unconnected-(U6-DOUT-Pad2)") (class "Default")
      (node (ref "U6") (pin "2") (pinfunction "DOUT_2") (pintype "input"))
    )
    (net (code "74") (name "unconnected-(U6-GND-Pad3)") (class "Default")
      (node (ref "U6") (pin "3") (pinfunction "GND_3") (pintype "input"))
    )
    (net (code "75") (name "unconnected-(U6-VDD-Pad1)") (class "Default")
      (node (ref "U6") (pin "1") (pinfunction "VDD_1") (pintype "input"))
    )
    (net (code "76") (name "unconnected-(U7-DIN-PadDI)") (class "Default")
      (node (ref "U7") (pin "DI") (pinfunction "DIN_DI") (pintype "input"))
    )
    (net (code "77") (name "unconnected-(U7-DOUT-PadDO)") (class "Default")
      (node (ref "U7") (pin "DO") (pinfunction "DOUT_DO") (pintype "input"))
    )
    (net (code "78") (name "unconnected-(U7-GND-PadG)") (class "Default")
      (node (ref "U7") (pin "G") (pinfunction "GND_G") (pintype "input"))
    )
    (net (code "79") (name "unconnected-(U7-VDD-PadV)") (class "Default")
      (node (ref "U7") (pin "V") (pinfunction "VDD_V") (pintype "input"))
    )
    (net (code "80") (name "unconnected-(U8-DIN-PadDI)") (class "Default")
      (node (ref "U8") (pin "DI") (pinfunction "DIN_DI") (pintype "input"))
    )
    (net (code "81") (name "unconnected-(U8-DOUT-PadDO)") (class "Default")
      (node (ref "U8") (pin "DO") (pinfunction "DOUT_DO") (pintype "input"))
    )
    (net (code "82") (name "unconnected-(U8-GND-PadG)") (class "Default")
      (node (ref "U8") (pin "G") (pinfunction "GND_G") (pintype "input"))
    )
    (net (code "83") (name "unconnected-(U8-VDD-PadV)") (class "Default")
      (node (ref "U8") (pin "V") (pinfunction "VDD_V") (pintype "input"))
    )
    (net (code "84") (name "unconnected-(U9-Pad1)") (class "Default")
      (node (ref "U9") (pin "1") (pinfunction "1_1") (pintype "input"))
    )
    (net (code "85") (name "unconnected-(U9-Pad2)") (class "Default")
      (node (ref "U9") (pin "2") (pinfunction "2_2") (pintype "input"))
    )
    (net (code "86") (name "unconnected-(U10-Pad1)") (class "Default")
      (node (ref "U10") (pin "1") (pinfunction "1_1") (pintype "input"))
    )
    (net (code "87") (name "unconnected-(U10-Pad2)") (class "Default")
      (node (ref "U10") (pin "2") (pinfunction "2_2") (pintype "input"))
    )
  )
)
